# Tarjeta5_NOOUTLINE.net
KiCad netlist of a schematic drawn in EAGLE
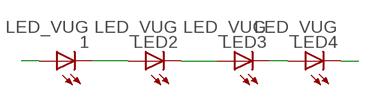
[diagram p0: schematic, sheet 1]

(export (version "E")
  (design (tool "Eeschema 10.0.6"))
  (components
    (comp (ref "1")
      (value "LED_VUG")
      (footprint "eagle-import:CINVESTAV_LUXEON")
      (libsource (lib "eagle-import") (part "LED_VUG"))
    )
    (comp (ref "LED2")
      (value "LED_VUG")
      (footprint "eagle-import:CINVESTAV_LUXEON")
      (libsource (lib "eagle-import") (part "LED_VUG"))
    )
    (comp (ref "LED3")
      (value "LED_VUG")
      (footprint "eagle-import:CINVESTAV_LUXEON")
      (libsource (lib "eagle-import") (part "LED_VUG"))
    )
    (comp (ref "LED4")
      (value "LED_VUG")
      (footprint "eagle-import:CINVESTAV_LUXEON")
      (libsource (lib "eagle-import") (part "LED_VUG"))
    )
  )
  (nets
    (net (code "1") (name "Net-(1-PadC)") (class "Default")
      (node (ref "1") (pin "C") (pinfunction "C_C") (pintype "passive"))
      (node (ref "LED2") (pin "A") (pinfunction "A_A") (pintype "passive"))
    )
    (net (code "2") (name "Net-(LED2-PadC)") (class "Default")
      (node (ref "LED2") (pin "C") (pinfunction "C_C") (pintype "passive"))
      (node (ref "LED3") (pin "A") (pinfunction "A_A") (pintype "passive"))
    )
    (net (code "3") (name "Net-(LED3-PadC)") (class "Default")
      (node (ref "LED3") (pin "C") (pinfunction "C_C") (pintype "passive"))
      (node (ref "LED4") (pin "A") (pinfunction "A_A") (pintype "passive"))
    )
    (net (code "4") (name "unconnected-(1-PadA)") (class "Default")
      (node (ref "1") (pin "A") (pinfunction "A_A") (pintype "passive"))
    )
    (net (code "5") (name "unconnected-(LED4-PadC)") (class "Default")
      (node (ref "LED4") (pin "C") (pinfunction "C_C") (pintype "passive"))
    )
  )
)
